# Jafar_Tester-Programmer_-_EasyEDA_-_Sche.net
KiCad netlist of a schematic drawn in EasyEDA
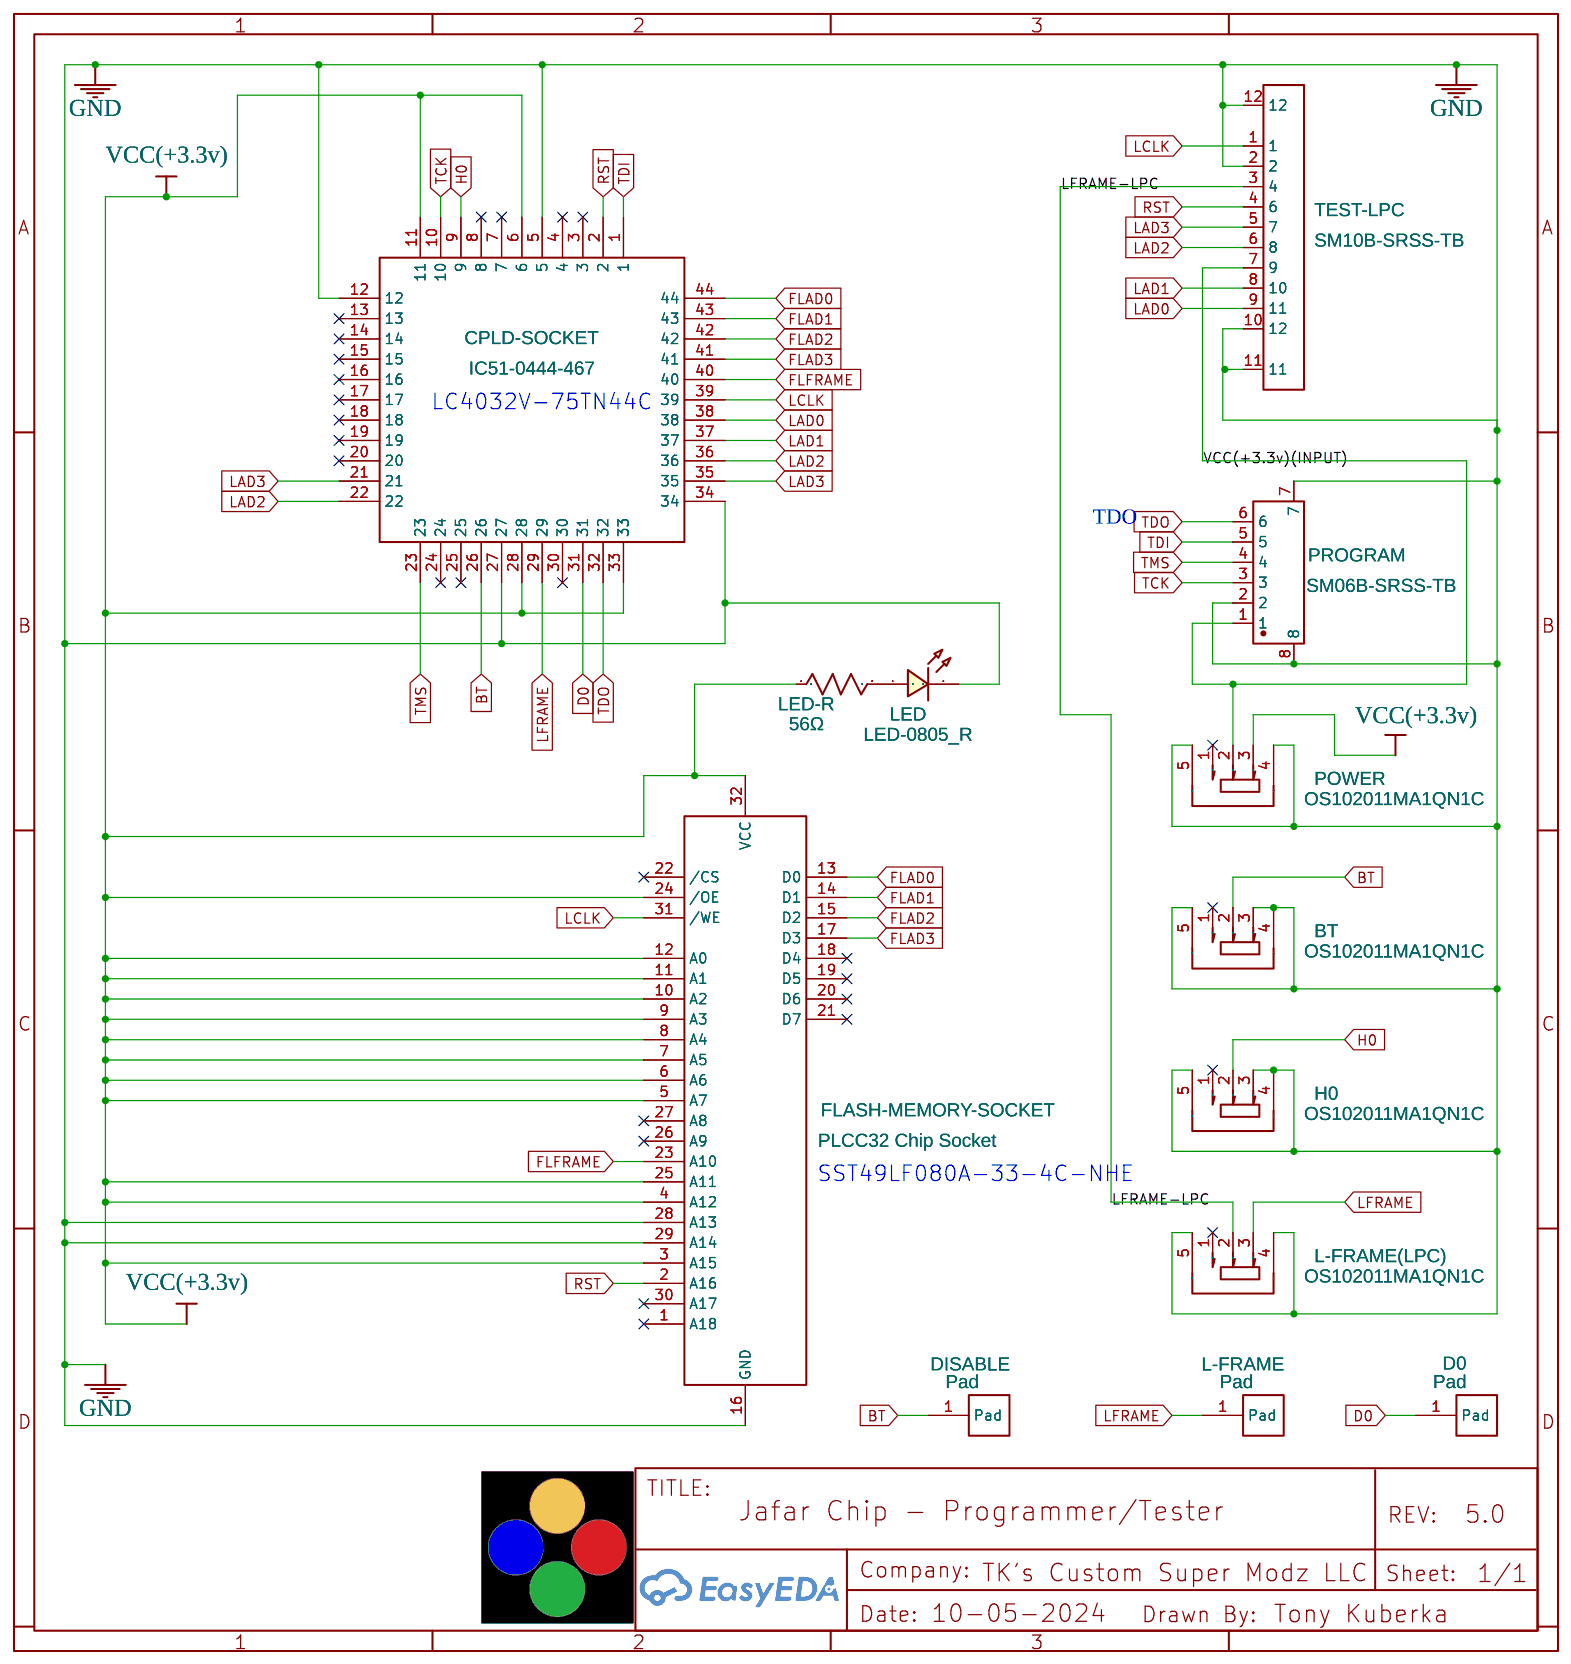
[diagram p0: schematic sheet]

(export (version "E")
  (design (tool "Eeschema 10.0.6"))
  (components
    (comp (ref "BT")
      (value "OS102011MA1QN1C")
      (fields (field (name "Manufacturer") "C&K"))
      (libsource (lib "") (part "OS102011MA1QN1C_3"))
    )
    (comp (ref "CPLD-SOCKET") (value "IC51-0444-467") (libsource (lib "") (part "IC51-0444-467 32U4")))
    (comp (ref "D0") (value "Pad") (libsource (lib "") (part "SOLDER PAD_1")))
    (comp (ref "DISABLE") (value "Pad") (libsource (lib "") (part "SOLDER PAD")))
    (comp (ref "FLASH-MEMORY-SOCKET")
      (value "PLCC32 Chip Socket")
      (fields
        (field (name "Manufacturer Part") "SST39VF040-70-4C-NHE")
        (field (name "Manufacturer") "Microchip Technology")
      )
      (libsource (lib "") (part "SST39VF040-70-4C-NHE"))
    )
    (comp (ref "H0")
      (value "OS102011MA1QN1C")
      (fields (field (name "Manufacturer") "C&K"))
      (libsource (lib "") (part "OS102011MA1QN1C_2"))
    )
    (comp (ref "L-FRAME") (value "Pad") (libsource (lib "") (part "SOLDER PAD_2")))
    (comp (ref "L-FRAME(LPC)")
      (value "OS102011MA1QN1C")
      (fields (field (name "Manufacturer") "C&K"))
      (libsource (lib "") (part "OS102011MA1QN1C_1"))
    )
    (comp (ref "LED")
      (value "LED-0805_R")
      (fields
        (field (name "Manufacturer Part") "17-21SURC/S530-A3/TR8")
        (field (name "Manufacturer") "EVERLIGHT(台湾亿光)")
      )
      (libsource (lib "") (part "LED-0805_R"))
    )
    (comp (ref "LED-R") (value "56Ω") (libsource (lib "") (part "R_0805_US")))
    (comp (ref "POWER")
      (value "OS102011MA1QN1C")
      (fields (field (name "Manufacturer") "C&K"))
      (libsource (lib "") (part "OS102011MA1QN1C"))
    )
    (comp (ref "PROGRAM")
      (value "SM06B-SRSS-TB")
      (fields (field (name "Manufacturer") "JST"))
      (libsource (lib "") (part "SM06B-SRSS-TB"))
    )
    (comp (ref "TEST-LPC")
      (value "SM10B-SRSS-TB")
      (fields (field (name "Manufacturer Part") "SM10B-SRSS-TB(LF)(SN)") (field (name "Manufacturer") "JST"))
      (libsource (lib "") (part "SM10B-SRSS-TB (LF)(SN)"))
    )
  )
  (nets
    (net (code "1") (name "/LFRAME-LPC") (class "Default")
      (node (ref "L-FRAME(LPC)") (pin "2") (pinfunction "2_2") (pintype "unspecified"))
      (node (ref "TEST-LPC") (pin "3") (pinfunction "4_3") (pintype "unspecified"))
    )
    (net (code "2") (name "/VCC(+3.3v)(INPUT)") (class "Default")
      (node (ref "POWER") (pin "2") (pinfunction "2_2") (pintype "unspecified"))
      (node (ref "PROGRAM") (pin "1") (pinfunction "1_1") (pintype "unspecified"))
      (node (ref "TEST-LPC") (pin "7") (pinfunction "9_7") (pintype "unspecified"))
    )
    (net (code "3") (name "BT") (class "Default")
      (node (ref "BT") (pin "2") (pinfunction "2_2") (pintype "unspecified"))
      (node (ref "CPLD-SOCKET") (pin "26") (pinfunction "26_26") (pintype "unspecified"))
      (node (ref "DISABLE") (pin "1") (pinfunction "Pad_1") (pintype "unspecified"))
    )
    (net (code "4") (name "D0") (class "Default")
      (node (ref "CPLD-SOCKET") (pin "31") (pinfunction "31_31") (pintype "unspecified"))
      (node (ref "D0") (pin "1") (pinfunction "Pad_1") (pintype "unspecified"))
    )
    (net (code "5") (name "FLAD0") (class "Default")
      (node (ref "CPLD-SOCKET") (pin "44") (pinfunction "44_44") (pintype "unspecified"))
      (node (ref "FLASH-MEMORY-SOCKET") (pin "13") (pinfunction "D0_13") (pintype "unspecified"))
    )
    (net (code "6") (name "FLAD1") (class "Default")
      (node (ref "CPLD-SOCKET") (pin "43") (pinfunction "43_43") (pintype "unspecified"))
      (node (ref "FLASH-MEMORY-SOCKET") (pin "14") (pinfunction "D1_14") (pintype "unspecified"))
    )
    (net (code "7") (name "FLAD2") (class "Default")
      (node (ref "CPLD-SOCKET") (pin "42") (pinfunction "42_42") (pintype "unspecified"))
      (node (ref "FLASH-MEMORY-SOCKET") (pin "15") (pinfunction "D2_15") (pintype "unspecified"))
    )
    (net (code "8") (name "FLAD3") (class "Default")
      (node (ref "CPLD-SOCKET") (pin "41") (pinfunction "41_41") (pintype "unspecified"))
      (node (ref "FLASH-MEMORY-SOCKET") (pin "17") (pinfunction "D3_17") (pintype "unspecified"))
    )
    (net (code "9") (name "FLFRAME") (class "Default")
      (node (ref "CPLD-SOCKET") (pin "40") (pinfunction "40_40") (pintype "unspecified"))
      (node (ref "FLASH-MEMORY-SOCKET") (pin "23") (pinfunction "A10_23") (pintype "unspecified"))
    )
    (net (code "10") (name "GND") (class "Default")
      (node (ref "BT") (pin "3") (pinfunction "3_3") (pintype "unspecified"))
      (node (ref "BT") (pin "4") (pinfunction "4_4") (pintype "unspecified"))
      (node (ref "BT") (pin "5") (pinfunction "5_5") (pintype "unspecified"))
      (node (ref "CPLD-SOCKET") (pin "12") (pinfunction "12_12") (pintype "unspecified"))
      (node (ref "CPLD-SOCKET") (pin "27") (pinfunction "27_27") (pintype "unspecified"))
      (node (ref "CPLD-SOCKET") (pin "34") (pinfunction "34_34") (pintype "unspecified"))
      (node (ref "CPLD-SOCKET") (pin "5") (pinfunction "5_5") (pintype "unspecified"))
      (node (ref "FLASH-MEMORY-SOCKET") (pin "16") (pinfunction "GND_16") (pintype "unspecified"))
      (node (ref "FLASH-MEMORY-SOCKET") (pin "28") (pinfunction "A13_28") (pintype "unspecified"))
      (node (ref "FLASH-MEMORY-SOCKET") (pin "29") (pinfunction "A14_29") (pintype "unspecified"))
      (node (ref "H0") (pin "3") (pinfunction "3_3") (pintype "unspecified"))
      (node (ref "H0") (pin "4") (pinfunction "4_4") (pintype "unspecified"))
      (node (ref "H0") (pin "5") (pinfunction "5_5") (pintype "unspecified"))
      (node (ref "L-FRAME(LPC)") (pin "4") (pinfunction "4_4") (pintype "unspecified"))
      (node (ref "L-FRAME(LPC)") (pin "5") (pinfunction "5_5") (pintype "unspecified"))
      (node (ref "LED") (pin "2") (pinfunction "2_2") (pintype "unspecified"))
      (node (ref "POWER") (pin "4") (pinfunction "4_4") (pintype "unspecified"))
      (node (ref "POWER") (pin "5") (pinfunction "5_5") (pintype "unspecified"))
      (node (ref "PROGRAM") (pin "2") (pinfunction "2_2") (pintype "unspecified"))
      (node (ref "PROGRAM") (pin "7") (pinfunction "7_7") (pintype "unspecified"))
      (node (ref "PROGRAM") (pin "8") (pinfunction "8_8") (pintype "unspecified"))
      (node (ref "TEST-LPC") (pin "10") (pinfunction "12_10") (pintype "unspecified"))
      (node (ref "TEST-LPC") (pin "11") (pinfunction "11_11") (pintype "unspecified"))
      (node (ref "TEST-LPC") (pin "12") (pinfunction "12_12") (pintype "unspecified"))
      (node (ref "TEST-LPC") (pin "2") (pinfunction "2_2") (pintype "unspecified"))
    )
    (net (code "11") (name "H0") (class "Default")
      (node (ref "CPLD-SOCKET") (pin "9") (pinfunction "9_9") (pintype "unspecified"))
      (node (ref "H0") (pin "2") (pinfunction "2_2") (pintype "unspecified"))
    )
    (net (code "12") (name "LAD0") (class "Default")
      (node (ref "CPLD-SOCKET") (pin "38") (pinfunction "38_38") (pintype "unspecified"))
      (node (ref "TEST-LPC") (pin "9") (pinfunction "11_9") (pintype "unspecified"))
    )
    (net (code "13") (name "LAD1") (class "Default")
      (node (ref "CPLD-SOCKET") (pin "37") (pinfunction "37_37") (pintype "unspecified"))
      (node (ref "TEST-LPC") (pin "8") (pinfunction "10_8") (pintype "unspecified"))
    )
    (net (code "14") (name "LAD2") (class "Default")
      (node (ref "CPLD-SOCKET") (pin "22") (pinfunction "22_22") (pintype "unspecified"))
      (node (ref "CPLD-SOCKET") (pin "36") (pinfunction "36_36") (pintype "unspecified"))
      (node (ref "TEST-LPC") (pin "6") (pinfunction "8_6") (pintype "unspecified"))
    )
    (net (code "15") (name "LAD3") (class "Default")
      (node (ref "CPLD-SOCKET") (pin "21") (pinfunction "21_21") (pintype "unspecified"))
      (node (ref "CPLD-SOCKET") (pin "35") (pinfunction "35_35") (pintype "unspecified"))
      (node (ref "TEST-LPC") (pin "5") (pinfunction "7_5") (pintype "unspecified"))
    )
    (net (code "16") (name "LCLK") (class "Default")
      (node (ref "CPLD-SOCKET") (pin "39") (pinfunction "39_39") (pintype "unspecified"))
      (node (ref "FLASH-MEMORY-SOCKET") (pin "31") (pinfunction "/WE_31") (pintype "unspecified"))
      (node (ref "TEST-LPC") (pin "1") (pinfunction "1_1") (pintype "unspecified"))
    )
    (net (code "17") (name "LFRAME") (class "Default")
      (node (ref "CPLD-SOCKET") (pin "29") (pinfunction "29_29") (pintype "unspecified"))
      (node (ref "L-FRAME") (pin "1") (pinfunction "Pad_1") (pintype "unspecified"))
      (node (ref "L-FRAME(LPC)") (pin "3") (pinfunction "3_3") (pintype "unspecified"))
    )
    (net (code "18") (name "Net-(LED-Pad1)") (class "Default")
      (node (ref "LED") (pin "1") (pinfunction "1_1") (pintype "unspecified"))
      (node (ref "LED-R") (pin "2") (pinfunction "2_2") (pintype "unspecified"))
    )
    (net (code "19") (name "RST") (class "Default")
      (node (ref "CPLD-SOCKET") (pin "2") (pinfunction "2_2") (pintype "unspecified"))
      (node (ref "FLASH-MEMORY-SOCKET") (pin "2") (pinfunction "A16_2") (pintype "unspecified"))
      (node (ref "TEST-LPC") (pin "4") (pinfunction "6_4") (pintype "unspecified"))
    )
    (net (code "20") (name "TCK") (class "Default")
      (node (ref "CPLD-SOCKET") (pin "10") (pinfunction "10_10") (pintype "unspecified"))
      (node (ref "PROGRAM") (pin "3") (pinfunction "3_3") (pintype "unspecified"))
    )
    (net (code "21") (name "TDI") (class "Default")
      (node (ref "CPLD-SOCKET") (pin "1") (pinfunction "1_1") (pintype "unspecified"))
      (node (ref "PROGRAM") (pin "5") (pinfunction "5_5") (pintype "unspecified"))
    )
    (net (code "22") (name "TDO") (class "Default")
      (node (ref "CPLD-SOCKET") (pin "32") (pinfunction "32_32") (pintype "unspecified"))
      (node (ref "PROGRAM") (pin "6") (pinfunction "6_6") (pintype "unspecified"))
    )
    (net (code "23") (name "TMS") (class "Default")
      (node (ref "CPLD-SOCKET") (pin "23") (pinfunction "23_23") (pintype "unspecified"))
      (node (ref "PROGRAM") (pin "4") (pinfunction "4_4") (pintype "unspecified"))
    )
    (net (code "24") (name "VCC(+3.3v)") (class "Default")
      (node (ref "CPLD-SOCKET") (pin "11") (pinfunction "11_11") (pintype "unspecified"))
      (node (ref "CPLD-SOCKET") (pin "28") (pinfunction "28_28") (pintype "unspecified"))
      (node (ref "CPLD-SOCKET") (pin "33") (pinfunction "33_33") (pintype "unspecified"))
      (node (ref "CPLD-SOCKET") (pin "6") (pinfunction "6_6") (pintype "unspecified"))
      (node (ref "FLASH-MEMORY-SOCKET") (pin "10") (pinfunction "A2_10") (pintype "unspecified"))
      (node (ref "FLASH-MEMORY-SOCKET") (pin "11") (pinfunction "A1_11") (pintype "unspecified"))
      (node (ref "FLASH-MEMORY-SOCKET") (pin "12") (pinfunction "A0_12") (pintype "unspecified"))
      (node (ref "FLASH-MEMORY-SOCKET") (pin "24") (pinfunction "/OE_24") (pintype "unspecified"))
      (node (ref "FLASH-MEMORY-SOCKET") (pin "25") (pinfunction "A11_25") (pintype "unspecified"))
      (node (ref "FLASH-MEMORY-SOCKET") (pin "3") (pinfunction "A15_3") (pintype "unspecified"))
      (node (ref "FLASH-MEMORY-SOCKET") (pin "32") (pinfunction "VCC_32") (pintype "unspecified"))
      (node (ref "FLASH-MEMORY-SOCKET") (pin "4") (pinfunction "A12_4") (pintype "unspecified"))
      (node (ref "FLASH-MEMORY-SOCKET") (pin "5") (pinfunction "A7_5") (pintype "unspecified"))
      (node (ref "FLASH-MEMORY-SOCKET") (pin "6") (pinfunction "A6_6") (pintype "unspecified"))
      (node (ref "FLASH-MEMORY-SOCKET") (pin "7") (pinfunction "A5_7") (pintype "unspecified"))
      (node (ref "FLASH-MEMORY-SOCKET") (pin "8") (pinfunction "A4_8") (pintype "unspecified"))
      (node (ref "FLASH-MEMORY-SOCKET") (pin "9") (pinfunction "A3_9") (pintype "unspecified"))
      (node (ref "LED-R") (pin "1") (pinfunction "1_1") (pintype "unspecified"))
      (node (ref "POWER") (pin "3") (pinfunction "3_3") (pintype "unspecified"))
    )
    (net (code "25") (name "unconnected-(BT-Pad1)") (class "Default")
      (node (ref "BT") (pin "1") (pinfunction "1_1") (pintype "unspecified+no_connect"))
    )
    (net (code "26") (name "unconnected-(CPLD-SOCKET-Pad3)") (class "Default")
      (node (ref "CPLD-SOCKET") (pin "3") (pinfunction "3_3") (pintype "unspecified+no_connect"))
    )
    (net (code "27") (name "unconnected-(CPLD-SOCKET-Pad4)") (class "Default")
      (node (ref "CPLD-SOCKET") (pin "4") (pinfunction "4_4") (pintype "unspecified+no_connect"))
    )
    (net (code "28") (name "unconnected-(CPLD-SOCKET-Pad7)") (class "Default")
      (node (ref "CPLD-SOCKET") (pin "7") (pinfunction "7_7") (pintype "unspecified+no_connect"))
    )
    (net (code "29") (name "unconnected-(CPLD-SOCKET-Pad8)") (class "Default")
      (node (ref "CPLD-SOCKET") (pin "8") (pinfunction "8_8") (pintype "unspecified+no_connect"))
    )
    (net (code "30") (name "unconnected-(CPLD-SOCKET-Pad13)") (class "Default")
      (node (ref "CPLD-SOCKET") (pin "13") (pinfunction "13_13") (pintype "unspecified+no_connect"))
    )
    (net (code "31") (name "unconnected-(CPLD-SOCKET-Pad14)") (class "Default")
      (node (ref "CPLD-SOCKET") (pin "14") (pinfunction "14_14") (pintype "unspecified+no_connect"))
    )
    (net (code "32") (name "unconnected-(CPLD-SOCKET-Pad15)") (class "Default")
      (node (ref "CPLD-SOCKET") (pin "15") (pinfunction "15_15") (pintype "unspecified+no_connect"))
    )
    (net (code "33") (name "unconnected-(CPLD-SOCKET-Pad16)") (class "Default")
      (node (ref "CPLD-SOCKET") (pin "16") (pinfunction "16_16") (pintype "unspecified+no_connect"))
    )
    (net (code "34") (name "unconnected-(CPLD-SOCKET-Pad17)") (class "Default")
      (node (ref "CPLD-SOCKET") (pin "17") (pinfunction "17_17") (pintype "unspecified+no_connect"))
    )
    (net (code "35") (name "unconnected-(CPLD-SOCKET-Pad18)") (class "Default")
      (node (ref "CPLD-SOCKET") (pin "18") (pinfunction "18_18") (pintype "unspecified+no_connect"))
    )
    (net (code "36") (name "unconnected-(CPLD-SOCKET-Pad19)") (class "Default")
      (node (ref "CPLD-SOCKET") (pin "19") (pinfunction "19_19") (pintype "unspecified+no_connect"))
    )
    (net (code "37") (name "unconnected-(CPLD-SOCKET-Pad20)") (class "Default")
      (node (ref "CPLD-SOCKET") (pin "20") (pinfunction "20_20") (pintype "unspecified+no_connect"))
    )
    (net (code "38") (name "unconnected-(CPLD-SOCKET-Pad24)") (class "Default")
      (node (ref "CPLD-SOCKET") (pin "24") (pinfunction "24_24") (pintype "unspecified+no_connect"))
    )
    (net (code "39") (name "unconnected-(CPLD-SOCKET-Pad25)") (class "Default")
      (node (ref "CPLD-SOCKET") (pin "25") (pinfunction "25_25") (pintype "unspecified+no_connect"))
    )
    (net (code "40") (name "unconnected-(CPLD-SOCKET-Pad30)") (class "Default")
      (node (ref "CPLD-SOCKET") (pin "30") (pinfunction "30_30") (pintype "unspecified+no_connect"))
    )
    (net (code "41") (name "unconnected-(FLASH-MEMORY-SOCKET-A8-Pad27)") (class "Default")
      (node (ref "FLASH-MEMORY-SOCKET") (pin "27") (pinfunction "A8_27") (pintype "unspecified+no_connect"))
    )
    (net (code "42") (name "unconnected-(FLASH-MEMORY-SOCKET-A9-Pad26)") (class "Default")
      (node (ref "FLASH-MEMORY-SOCKET") (pin "26") (pinfunction "A9_26") (pintype "unspecified+no_connect"))
    )
    (net (code "43") (name "unconnected-(FLASH-MEMORY-SOCKET-A17-Pad30)") (class "Default")
      (node (ref "FLASH-MEMORY-SOCKET") (pin "30") (pinfunction "A17_30") (pintype "unspecified+no_connect"))
    )
    (net (code "44") (name "unconnected-(FLASH-MEMORY-SOCKET-A18-Pad1)") (class "Default")
      (node (ref "FLASH-MEMORY-SOCKET") (pin "1") (pinfunction "A18_1") (pintype "unspecified+no_connect"))
    )
    (net (code "45") (name "unconnected-(FLASH-MEMORY-SOCKET-D4-Pad18)") (class "Default")
      (node (ref "FLASH-MEMORY-SOCKET") (pin "18") (pinfunction "D4_18") (pintype "unspecified+no_connect"))
    )
    (net (code "46") (name "unconnected-(FLASH-MEMORY-SOCKET-D5-Pad19)") (class "Default")
      (node (ref "FLASH-MEMORY-SOCKET") (pin "19") (pinfunction "D5_19") (pintype "unspecified+no_connect"))
    )
    (net (code "47") (name "unconnected-(FLASH-MEMORY-SOCKET-D6-Pad20)") (class "Default")
      (node (ref "FLASH-MEMORY-SOCKET") (pin "20") (pinfunction "D6_20") (pintype "unspecified+no_connect"))
    )
    (net (code "48") (name "unconnected-(FLASH-MEMORY-SOCKET-D7-Pad21)") (class "Default")
      (node (ref "FLASH-MEMORY-SOCKET") (pin "21") (pinfunction "D7_21") (pintype "unspecified+no_connect"))
    )
    (net (code "49") (name "unconnected-(FLASH-MEMORY-SOCKET-{slash}CS-Pad22)") (class "Default")
      (node (ref "FLASH-MEMORY-SOCKET") (pin "22") (pinfunction "/CS_22") (pintype "unspecified+no_connect"))
    )
    (net (code "50") (name "unconnected-(H0-Pad1)") (class "Default")
      (node (ref "H0") (pin "1") (pinfunction "1_1") (pintype "unspecified+no_connect"))
    )
    (net (code "51") (name "unconnected-(L-FRAME(LPC)-Pad1)") (class "Default")
      (node (ref "L-FRAME(LPC)") (pin "1") (pinfunction "1_1") (pintype "unspecified+no_connect"))
    )
    (net (code "52") (name "unconnected-(POWER-Pad1)") (class "Default")
      (node (ref "POWER") (pin "1") (pinfunction "1_1") (pintype "unspecified+no_connect"))
    )
  )
)
